# Power.net
KiCad netlist of a schematic drawn in Altium Designer
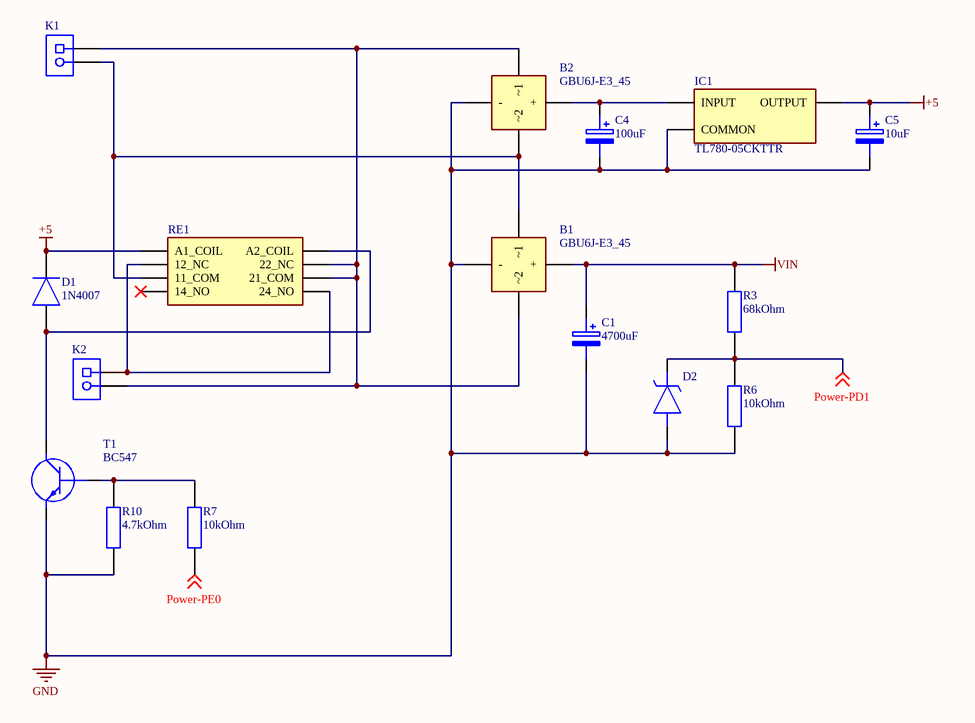
[diagram p0: Power.SchDoc]

(export (version "E")
  (design (tool "Eeschema 10.0.6"))
  (components
    (comp (ref "B1")
      (value "GBU6J-E3_45")
      (footprint "PcbLib1:GBU6JE345")
      (description "Bridge Rectifier")
      (fields (field (name "MANUFACTURER_PART_NUMBER") "GBU6J-E3/45"))
      (libsource (lib "Schlib1") (part "GBU6J-E3_45"))
    )
    (comp (ref "B2")
      (value "GBU6J-E3_45")
      (footprint "PcbLib1:GBU6JE345")
      (description "Bridge Rectifier")
      (fields (field (name "MANUFACTURER_PART_NUMBER") "GBU6J-E3/45"))
      (libsource (lib "Schlib1") (part "GBU6J-E3_45"))
    )
    (comp (ref "C1")
      (value "4700uF")
      (footprint "4700uF capacitor")
      (description "Capacitor Polarised")
      (fields (field (name "MANUFACTURER_PART_NUMBER") "UVR1H472MRD"))
      (libsource (lib "Schlib1") (part "4700uF capacitor"))
    )
    (comp (ref "C4")
      (value "100uF")
      (footprint "100uF capacitor")
      (description "Capacitor Polarised")
      (fields (field (name "MANUFACTURER_PART_NUMBER") "ESK107M050AG3EA"))
      (libsource (lib "Schlib1") (part "100uF capacitor"))
    )
    (comp (ref "C5")
      (value "10uF")
      (footprint "10uF capacitor")
      (description "Capacitor Polarised")
      (fields
        (field (name "MOUSER2 PART NUMBER") "667-ECA-1HM100B")
        (field (name "MANUFACTURER_PART_NUMBER") "ECA-1HM100B")
      )
      (libsource (lib "Schlib1") (part "10uF capacitor"))
    )
    (comp (ref "D1")
      (value "1N4007")
      (footprint "0.77mm lead diode")
      (description "Diode")
      (fields (field (name "MOUSER PART NUMBER") "637-1N4007"))
      (libsource (lib "Schlib1") (part "1N4007"))
    )
    (comp (ref "D2")
      (value "1N5231B")
      (footprint "0.5mm lead diode")
      (description "Zener Diode")
      (libsource (lib "Schlib1") (part "1N5231B"))
    )
    (comp (ref "IC1")
      (value "TL780-05CKTTR")
      (footprint "PcbLib1:TL78005CKTTR")
      (description "DC Converter")
      (libsource (lib "Schlib1") (part "TL780-05CKTTR"))
    )
    (comp (ref "K1")
      (value "1729128")
      (footprint "2-pin terminal block")
      (description "PCB Terminal Block, 13.5 A, 400 V, 2-Pin THD, RoHS, Bulk")
      (fields (field (name "MANUFACTURER") "Phoenix Contact"))
      (libsource (lib "Schlib1") (part "MKDSN 1,5/ 2-5,08"))
    )
    (comp (ref "K2")
      (value "1729128")
      (footprint "2-pin terminal block")
      (description "PCB Terminal Block, 13.5 A, 400 V, 2-Pin THD, RoHS, Bulk")
      (fields (field (name "MANUFACTURER") "Phoenix Contact"))
      (libsource (lib "Schlib1") (part "MKDSN 1,5/ 2-5,08"))
    )
    (comp (ref "R3")
      (value "68kOhm")
      (footprint "resistor")
      (description "Resistor")
      (fields (field (name "MANUFACTURER_PART_NUMBER") "CFR-25JR-52-68K"))
      (libsource (lib "Schlib1") (part "68kOhm resistor"))
    )
    (comp (ref "R6")
      (value "10kOhm")
      (footprint "resistor")
      (description "Resistor")
      (fields (field (name "MANUFACTURER_PART_NUMBER") "CFR-25JT-52-10K"))
      (libsource (lib "Schlib1") (part "10kOhm resistor"))
    )
    (comp (ref "R7")
      (value "10kOhm")
      (footprint "resistor")
      (description "Resistor")
      (fields (field (name "MANUFACTURER_PART_NUMBER") "CFR-25JT-52-10K"))
      (libsource (lib "Schlib1") (part "10kOhm"))
    )
    (comp (ref "R10")
      (value "4.7kOhm")
      (footprint "resistor")
      (description "Resistor")
      (fields
        (field (name "MOUSER2 PART NUMBER") "603-CFR-25JT-52-4K7")
        (field (name "MANUFACTURER_PART_NUMBER") "CFR-25JT-52-4K7")
      )
      (libsource (lib "Schlib1") (part "4.7kOhm"))
    )
    (comp (ref "RE1")
      (value "RT424005")
      (footprint "PcbLib1:RT42")
      (description "Relay")
      (fields (field (name "MOUSER2 PART NUMBER") "655-RT424005"))
      (libsource (lib "Schlib1") (part "RT424005"))
    )
    (comp (ref "T1")
      (value "BC547")
      (footprint "PcbLib1:BC547CBU")
      (description "Transistor BJT NPN")
      (fields (field (name "MANUFACTURER_PART_NUMBER") "BC547CBU"))
      (libsource (lib "Schlib1") (part "BC547"))
    )
  )
  (nets
    (net (code "1") (name "+5") (class "Default")
      (node (ref "C5") (pin "1") (pinfunction "+_1") (pintype "passive"))
      (node (ref "D1") (pin "1") (pinfunction "K_1") (pintype "passive"))
      (node (ref "IC1") (pin "3") (pinfunction "OUTPUT_3") (pintype "passive"))
      (node (ref "RE1") (pin "1") (pinfunction "A1_COIL_1") (pintype "passive"))
    )
    (net (code "2") (name "GND") (class "Default")
      (node (ref "B1") (pin "4") (pinfunction "-_4") (pintype "passive"))
      (node (ref "B2") (pin "4") (pinfunction "-_4") (pintype "passive"))
      (node (ref "C1") (pin "2") (pinfunction "-_2") (pintype "passive"))
      (node (ref "C4") (pin "2") (pinfunction "-_2") (pintype "passive"))
      (node (ref "C5") (pin "2") (pinfunction "-_2") (pintype "passive"))
      (node (ref "D2") (pin "2") (pinfunction "A_2") (pintype "passive"))
      (node (ref "IC1") (pin "2") (pinfunction "COMMON_2") (pintype "passive"))
      (node (ref "R10") (pin "1") (pinfunction "1_1") (pintype "passive"))
      (node (ref "R6") (pin "1") (pinfunction "1_1") (pintype "passive"))
      (node (ref "T1") (pin "3") (pinfunction "E_3") (pintype "passive"))
    )
    (net (code "3") (name "Net-(B1-~1)") (class "Default")
      (node (ref "B1") (pin "2") (pinfunction "~1_2") (pintype "passive"))
      (node (ref "B2") (pin "3") (pinfunction "~2_3") (pintype "passive"))
      (node (ref "K1") (pin "2") (pinfunction "2_2") (pintype "passive"))
      (node (ref "RE1") (pin "3") (pinfunction "11_COM_3") (pintype "passive"))
    )
    (net (code "4") (name "Net-(B1-~2)") (class "Default")
      (node (ref "B1") (pin "3") (pinfunction "~2_3") (pintype "passive"))
      (node (ref "B2") (pin "2") (pinfunction "~1_2") (pintype "passive"))
      (node (ref "K1") (pin "1") (pinfunction "1_1") (pintype "passive"))
      (node (ref "K2") (pin "2") (pinfunction "2_2") (pintype "passive"))
      (node (ref "RE1") (pin "6") (pinfunction "21_COM_6") (pintype "passive"))
      (node (ref "RE1") (pin "7") (pinfunction "22_NC_7") (pintype "passive"))
    )
    (net (code "5") (name "Net-(B2-+)") (class "Default")
      (node (ref "B2") (pin "1") (pinfunction "+_1") (pintype "passive"))
      (node (ref "C4") (pin "1") (pinfunction "+_1") (pintype "passive"))
      (node (ref "IC1") (pin "1") (pinfunction "INPUT_1") (pintype "passive"))
    )
    (net (code "6") (name "Net-(D1-A)") (class "Default")
      (node (ref "D1") (pin "2") (pinfunction "A_2") (pintype "passive"))
      (node (ref "RE1") (pin "8") (pinfunction "A2_COIL_8") (pintype "passive"))
      (node (ref "T1") (pin "1") (pinfunction "C_1") (pintype "passive"))
    )
    (net (code "7") (name "Net-(RE1-12_NC)") (class "Default")
      (node (ref "K2") (pin "1") (pinfunction "1_1") (pintype "passive"))
      (node (ref "RE1") (pin "2") (pinfunction "12_NC_2") (pintype "passive"))
      (node (ref "RE1") (pin "5") (pinfunction "24_NO_5") (pintype "passive"))
    )
    (net (code "8") (name "Net-(T1-B)") (class "Default")
      (node (ref "R10") (pin "2") (pinfunction "2_2") (pintype "passive"))
      (node (ref "R7") (pin "2") (pinfunction "2_2") (pintype "passive"))
      (node (ref "T1") (pin "2") (pinfunction "B_2") (pintype "passive"))
    )
    (net (code "9") (name "Power-PD1") (class "Default")
      (node (ref "D2") (pin "1") (pinfunction "K_1") (pintype "passive"))
      (node (ref "R3") (pin "1") (pinfunction "1_1") (pintype "passive"))
      (node (ref "R6") (pin "2") (pinfunction "2_2") (pintype "passive"))
    )
    (net (code "10") (name "Power-PE0") (class "Default")
      (node (ref "R7") (pin "1") (pinfunction "1_1") (pintype "passive"))
    )
    (net (code "11") (name "VIN") (class "Default")
      (node (ref "B1") (pin "1") (pinfunction "+_1") (pintype "passive"))
      (node (ref "C1") (pin "1") (pinfunction "+_1") (pintype "passive"))
      (node (ref "R3") (pin "2") (pinfunction "2_2") (pintype "passive"))
    )
    (net (code "12") (name "unconnected-(RE1-14_NO-Pad4)") (class "Default")
      (node (ref "RE1") (pin "4") (pinfunction "14_NO_4") (pintype "passive+no_connect"))
    )
  )
)
